# Button.net
KiCad netlist of a schematic drawn in Altium Designer
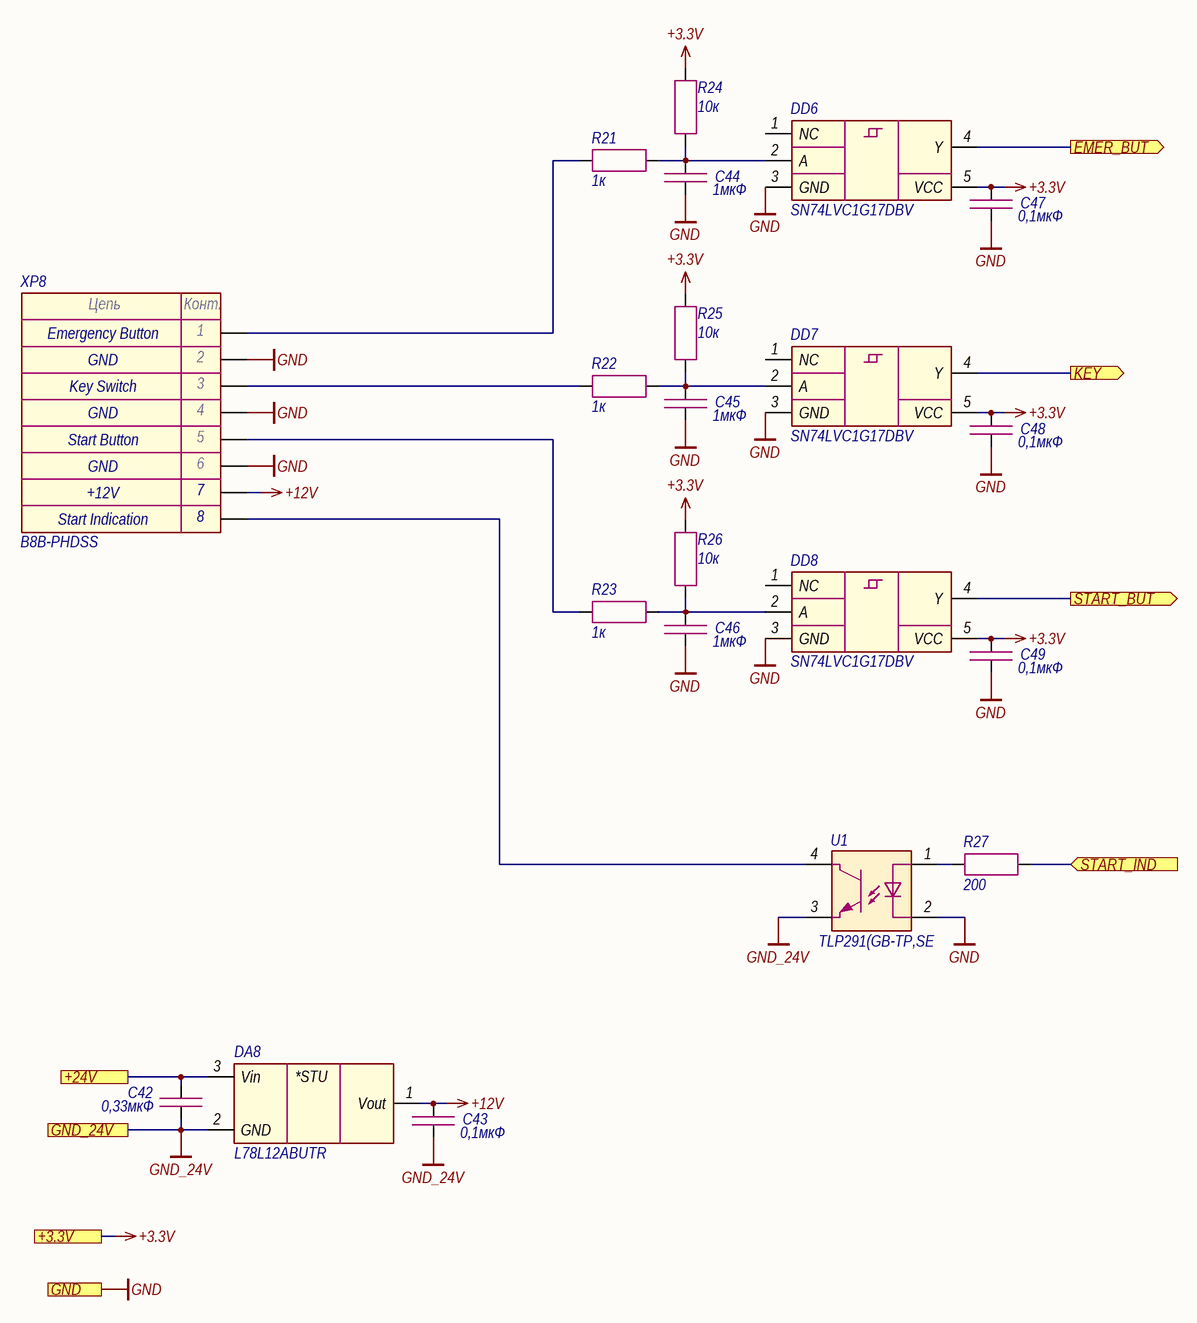
[diagram p0: Button.SchDoc]

(export (version "E")
  (design (tool "Eeschema 10.0.6"))
  (components
    (comp (ref "C42")
      (value "0,33мкФ")
      (footprint "Pcb_library:CAP_0805")
      (fields (field (name "MANUFACTURER") "Murata"))
      (libsource (lib "Schem_library") (part "Capacitor"))
    )
    (comp (ref "C43")
      (value "0,1мкФ")
      (footprint "Pcb_library:CAP_0603")
      (fields (field (name "MANUFACTURER") "Murata"))
      (libsource (lib "Schem_library") (part "Capacitor"))
    )
    (comp (ref "C44")
      (value "1мкФ")
      (footprint "Pcb_library:CAP_0603")
      (fields (field (name "MANUFACTURER") "Murata"))
      (libsource (lib "Schem_library") (part "Capacitor"))
    )
    (comp (ref "C45")
      (value "1мкФ")
      (footprint "Pcb_library:CAP_0603")
      (fields (field (name "MANUFACTURER") "Murata"))
      (libsource (lib "Schem_library") (part "Capacitor"))
    )
    (comp (ref "C46")
      (value "1мкФ")
      (footprint "Pcb_library:CAP_0603")
      (fields (field (name "MANUFACTURER") "Murata"))
      (libsource (lib "Schem_library") (part "Capacitor"))
    )
    (comp (ref "C47")
      (value "0,1мкФ")
      (footprint "Pcb_library:CAP_0603")
      (fields (field (name "MANUFACTURER") "Murata"))
      (libsource (lib "Schem_library") (part "Capacitor"))
    )
    (comp (ref "C48")
      (value "0,1мкФ")
      (footprint "Pcb_library:CAP_0603")
      (fields (field (name "MANUFACTURER") "Murata"))
      (libsource (lib "Schem_library") (part "Capacitor"))
    )
    (comp (ref "C49")
      (value "0,1мкФ")
      (footprint "Pcb_library:CAP_0603")
      (fields (field (name "MANUFACTURER") "Murata"))
      (libsource (lib "Schem_library") (part "Capacitor"))
    )
    (comp (ref "DA8")
      (value "L78L12ABUTR")
      (footprint "Pcb_library:SOT-89")
      (fields (field (name "MANUFACTURER") "STMicroelectronics"))
      (libsource (lib "Schem_library") (part "LD2981ABU50TR"))
    )
    (comp (ref "DD6")
      (value "SN74LVC1G17DBV")
      (footprint "Pcb_library:SOT-23-5")
      (fields (field (name "MANUFACTURER") "Texas Instruments"))
      (libsource (lib "Schem_library") (part "SN74LVC1G17"))
    )
    (comp (ref "DD7")
      (value "SN74LVC1G17DBV")
      (footprint "Pcb_library:SOT-23-5")
      (fields (field (name "MANUFACTURER") "Texas Instruments"))
      (libsource (lib "Schem_library") (part "SN74LVC1G17"))
    )
    (comp (ref "DD8")
      (value "SN74LVC1G17DBV")
      (footprint "Pcb_library:SOT-23-5")
      (fields (field (name "MANUFACTURER") "Texas Instruments"))
      (libsource (lib "Schem_library") (part "SN74LVC1G17"))
    )
    (comp (ref "R21")
      (value "1к")
      (footprint "Pcb_library:RES_0603")
      (fields (field (name "MANUFACTURER") "Yageo"))
      (libsource (lib "Schem_library") (part "Resistor"))
    )
    (comp (ref "R22")
      (value "1к")
      (footprint "Pcb_library:RES_0603")
      (fields (field (name "MANUFACTURER") "Yageo"))
      (libsource (lib "Schem_library") (part "Resistor"))
    )
    (comp (ref "R23")
      (value "1к")
      (footprint "Pcb_library:RES_0603")
      (fields (field (name "MANUFACTURER") "Yageo"))
      (libsource (lib "Schem_library") (part "Resistor"))
    )
    (comp (ref "R24")
      (value "10к")
      (footprint "Pcb_library:RES_0603")
      (fields (field (name "MANUFACTURER") "Yageo"))
      (libsource (lib "Schem_library") (part "Resistor"))
    )
    (comp (ref "R25")
      (value "10к")
      (footprint "Pcb_library:RES_0603")
      (fields (field (name "MANUFACTURER") "Yageo"))
      (libsource (lib "Schem_library") (part "Resistor"))
    )
    (comp (ref "R26")
      (value "10к")
      (footprint "Pcb_library:RES_0603")
      (fields (field (name "MANUFACTURER") "Yageo"))
      (libsource (lib "Schem_library") (part "Resistor"))
    )
    (comp (ref "R27")
      (value "200")
      (footprint "Pcb_library:RES_0603")
      (fields (field (name "MANUFACTURER") "Yageo"))
      (libsource (lib "Schem_library") (part "Resistor"))
    )
    (comp (ref "U1")
      (value "TLP291(GB-TP,SE")
      (footprint "Pcb_library:11-3C1")
      (fields (field (name "MANUFACTURER") "Toshiba"))
      (libsource (lib "Schem_library") (part "TLP291"))
    )
    (comp (ref "XP8")
      (value "B8B-PHDSS")
      (footprint "Pcb_library:B8B-PHDSS")
      (fields (field (name "MANUFACTURER") "JST"))
      (libsource (lib "Schem_library") (part "Connector-8"))
    )
  )
  (nets
    (net (code "1") (name "+3.3V") (class "Default")
      (node (ref "C47") (pin "1") (pinfunction "1_1") (pintype "passive"))
      (node (ref "C48") (pin "1") (pinfunction "1_1") (pintype "passive"))
      (node (ref "C49") (pin "1") (pinfunction "1_1") (pintype "passive"))
      (node (ref "DD6") (pin "5") (pinfunction "VCC_5") (pintype "passive"))
      (node (ref "DD7") (pin "5") (pinfunction "VCC_5") (pintype "passive"))
      (node (ref "DD8") (pin "5") (pinfunction "VCC_5") (pintype "passive"))
      (node (ref "R24") (pin "2") (pinfunction "2_2") (pintype "passive"))
      (node (ref "R25") (pin "2") (pinfunction "2_2") (pintype "passive"))
      (node (ref "R26") (pin "2") (pinfunction "2_2") (pintype "passive"))
    )
    (net (code "2") (name "+12V") (class "Default")
      (node (ref "C43") (pin "1") (pinfunction "1_1") (pintype "passive"))
      (node (ref "DA8") (pin "1") (pinfunction "Vout_1") (pintype "passive"))
      (node (ref "XP8") (pin "7") (pintype "passive"))
    )
    (net (code "3") (name "/+24V") (class "Default")
      (node (ref "C42") (pin "2") (pinfunction "2_2") (pintype "passive"))
      (node (ref "DA8") (pin "3") (pinfunction "Vin_3") (pintype "passive"))
    )
    (net (code "4") (name "/EMER_BUT") (class "Default")
      (node (ref "DD6") (pin "4") (pinfunction "Y_4") (pintype "passive"))
    )
    (net (code "5") (name "/KEY") (class "Default")
      (node (ref "DD7") (pin "4") (pinfunction "Y_4") (pintype "passive"))
    )
    (net (code "6") (name "/START_BUT") (class "Default")
      (node (ref "DD8") (pin "4") (pinfunction "Y_4") (pintype "passive"))
    )
    (net (code "7") (name "/START_IND") (class "Default")
      (node (ref "R27") (pin "2") (pinfunction "2_2") (pintype "passive"))
    )
    (net (code "8") (name "GND") (class "Default")
      (node (ref "C44") (pin "2") (pinfunction "2_2") (pintype "passive"))
      (node (ref "C45") (pin "2") (pinfunction "2_2") (pintype "passive"))
      (node (ref "C46") (pin "2") (pinfunction "2_2") (pintype "passive"))
      (node (ref "C47") (pin "2") (pinfunction "2_2") (pintype "passive"))
      (node (ref "C48") (pin "2") (pinfunction "2_2") (pintype "passive"))
      (node (ref "C49") (pin "2") (pinfunction "2_2") (pintype "passive"))
      (node (ref "DD6") (pin "3") (pinfunction "GND_3") (pintype "passive"))
      (node (ref "DD7") (pin "3") (pinfunction "GND_3") (pintype "passive"))
      (node (ref "DD8") (pin "3") (pinfunction "GND_3") (pintype "passive"))
      (node (ref "U1") (pin "2") (pintype "passive"))
      (node (ref "XP8") (pin "2") (pintype "passive"))
      (node (ref "XP8") (pin "4") (pintype "passive"))
      (node (ref "XP8") (pin "6") (pintype "passive"))
    )
    (net (code "9") (name "GND_24V") (class "Default")
      (node (ref "C42") (pin "1") (pinfunction "1_1") (pintype "passive"))
      (node (ref "C43") (pin "2") (pinfunction "2_2") (pintype "passive"))
      (node (ref "DA8") (pin "2") (pinfunction "GND_2") (pintype "passive"))
      (node (ref "U1") (pin "3") (pintype "passive"))
    )
    (net (code "10") (name "Net-(DD6-A)") (class "Default")
      (node (ref "C44") (pin "1") (pinfunction "1_1") (pintype "passive"))
      (node (ref "DD6") (pin "2") (pinfunction "A_2") (pintype "passive"))
      (node (ref "R21") (pin "2") (pinfunction "2_2") (pintype "passive"))
      (node (ref "R24") (pin "1") (pinfunction "1_1") (pintype "passive"))
    )
    (net (code "11") (name "Net-(DD7-A)") (class "Default")
      (node (ref "C45") (pin "1") (pinfunction "1_1") (pintype "passive"))
      (node (ref "DD7") (pin "2") (pinfunction "A_2") (pintype "passive"))
      (node (ref "R22") (pin "2") (pinfunction "2_2") (pintype "passive"))
      (node (ref "R25") (pin "1") (pinfunction "1_1") (pintype "passive"))
    )
    (net (code "12") (name "Net-(DD8-A)") (class "Default")
      (node (ref "C46") (pin "1") (pinfunction "1_1") (pintype "passive"))
      (node (ref "DD8") (pin "2") (pinfunction "A_2") (pintype "passive"))
      (node (ref "R23") (pin "2") (pinfunction "2_2") (pintype "passive"))
      (node (ref "R26") (pin "1") (pinfunction "1_1") (pintype "passive"))
    )
    (net (code "13") (name "Net-(R21-Pad1)") (class "Default")
      (node (ref "R21") (pin "1") (pinfunction "1_1") (pintype "passive"))
      (node (ref "XP8") (pin "1") (pintype "passive"))
    )
    (net (code "14") (name "Net-(R22-Pad1)") (class "Default")
      (node (ref "R22") (pin "1") (pinfunction "1_1") (pintype "passive"))
      (node (ref "XP8") (pin "3") (pintype "passive"))
    )
    (net (code "15") (name "Net-(R23-Pad1)") (class "Default")
      (node (ref "R23") (pin "1") (pinfunction "1_1") (pintype "passive"))
      (node (ref "XP8") (pin "5") (pintype "passive"))
    )
    (net (code "16") (name "Net-(R27-Pad1)") (class "Default")
      (node (ref "R27") (pin "1") (pinfunction "1_1") (pintype "passive"))
      (node (ref "U1") (pin "1") (pintype "passive"))
    )
    (net (code "17") (name "Net-(U1-Pad4)") (class "Default")
      (node (ref "U1") (pin "4") (pintype "passive"))
      (node (ref "XP8") (pin "8") (pintype "passive"))
    )
    (net (code "18") (name "unconnected-(DD6-NC-Pad1)") (class "Default")
      (node (ref "DD6") (pin "1") (pinfunction "NC_1") (pintype "passive"))
    )
    (net (code "19") (name "unconnected-(DD7-NC-Pad1)") (class "Default")
      (node (ref "DD7") (pin "1") (pinfunction "NC_1") (pintype "passive"))
    )
    (net (code "20") (name "unconnected-(DD8-NC-Pad1)") (class "Default")
      (node (ref "DD8") (pin "1") (pinfunction "NC_1") (pintype "passive"))
    )
  )
)
